# board_design.net
KiCad netlist of a schematic drawn in EAGLE
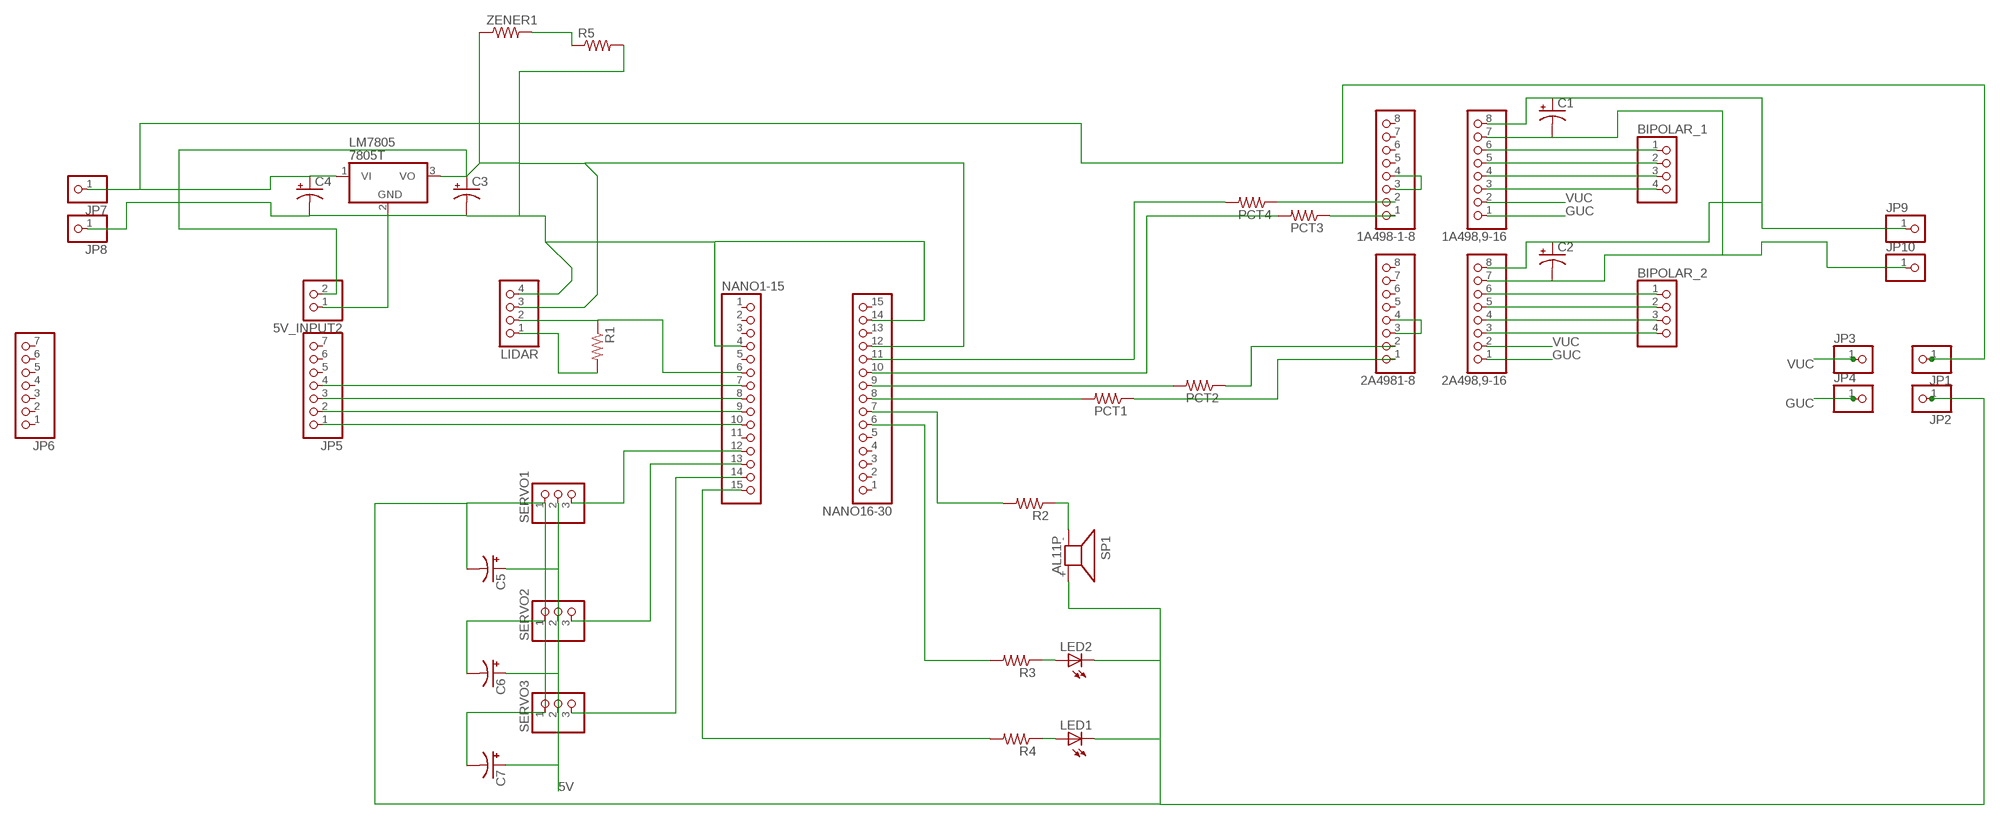
[diagram p0: schematic, sheet 1]

(export (version "E")
  (design (tool "Eeschema 10.0.6"))
  (components
    (comp (ref "1A498,9-16")
      (value "PINHD-1X8")
      (footprint "eagle-import:1X08")
      (libsource (lib "eagle-import") (part "PINHD-1X8"))
    )
    (comp (ref "1A498-1-8")
      (value "PINHD-1X8")
      (footprint "eagle-import:1X08")
      (libsource (lib "eagle-import") (part "PINHD-1X8"))
    )
    (comp (ref "2A498,9-16")
      (value "PINHD-1X8")
      (footprint "eagle-import:1X08")
      (libsource (lib "eagle-import") (part "PINHD-1X8"))
    )
    (comp (ref "2A4981-8")
      (value "PINHD-1X8")
      (footprint "eagle-import:1X08")
      (libsource (lib "eagle-import") (part "PINHD-1X8"))
    )
    (comp (ref "5V_INPUT2")
      (value "PINHD-1X2")
      (footprint "eagle-import:1X02")
      (libsource (lib "eagle-import") (part "PINHD-1X2"))
    )
    (comp (ref "BIPOLAR_1")
      (value "PINHD-1X4")
      (footprint "eagle-import:1X04")
      (libsource (lib "eagle-import") (part "PINHD-1X4"))
    )
    (comp (ref "BIPOLAR_2")
      (value "PINHD-1X4")
      (footprint "eagle-import:1X04")
      (libsource (lib "eagle-import") (part "PINHD-1X4"))
    )
    (comp (ref "C1")
      (value "CPOL-USE2.5-7")
      (footprint "eagle-import:E2,5-7")
      (libsource (lib "eagle-import") (part "CPOL-USE2.5-7"))
    )
    (comp (ref "C2")
      (value "CPOL-USE2.5-7")
      (footprint "eagle-import:E2,5-7")
      (libsource (lib "eagle-import") (part "CPOL-USE2.5-7"))
    )
    (comp (ref "C3")
      (value "CPOL-USE2.5-7")
      (footprint "eagle-import:E2,5-7")
      (libsource (lib "eagle-import") (part "CPOL-USE2.5-7"))
    )
    (comp (ref "C4")
      (value "CPOL-USE2.5-7")
      (footprint "eagle-import:E2,5-7")
      (libsource (lib "eagle-import") (part "CPOL-USE2.5-7"))
    )
    (comp (ref "C5")
      (value "CPOL-USE2.5-7")
      (footprint "eagle-import:E2,5-7")
      (libsource (lib "eagle-import") (part "CPOL-USE2.5-7"))
    )
    (comp (ref "C6")
      (value "CPOL-USE2.5-7")
      (footprint "eagle-import:E2,5-7")
      (libsource (lib "eagle-import") (part "CPOL-USE2.5-7"))
    )
    (comp (ref "C7")
      (value "CPOL-USE2.5-7")
      (footprint "eagle-import:E2,5-7")
      (libsource (lib "eagle-import") (part "CPOL-USE2.5-7"))
    )
    (comp (ref "JP1")
      (value "PINHD-1X1")
      (footprint "eagle-import:1X01")
      (libsource (lib "eagle-import") (part "PINHD-1X1"))
    )
    (comp (ref "JP2")
      (value "PINHD-1X1")
      (footprint "eagle-import:1X01")
      (libsource (lib "eagle-import") (part "PINHD-1X1"))
    )
    (comp (ref "JP3")
      (value "PINHD-1X1")
      (footprint "eagle-import:1X01")
      (libsource (lib "eagle-import") (part "PINHD-1X1"))
    )
    (comp (ref "JP4")
      (value "PINHD-1X1")
      (footprint "eagle-import:1X01")
      (libsource (lib "eagle-import") (part "PINHD-1X1"))
    )
    (comp (ref "JP5")
      (value "PINHD-1X7")
      (footprint "eagle-import:1X07")
      (libsource (lib "eagle-import") (part "PINHD-1X7"))
    )
    (comp (ref "JP6")
      (value "PINHD-1X7")
      (footprint "eagle-import:1X07")
      (libsource (lib "eagle-import") (part "PINHD-1X7"))
    )
    (comp (ref "JP7")
      (value "PINHD-1X1")
      (footprint "eagle-import:1X01")
      (libsource (lib "eagle-import") (part "PINHD-1X1"))
    )
    (comp (ref "JP8")
      (value "PINHD-1X1")
      (footprint "eagle-import:1X01")
      (libsource (lib "eagle-import") (part "PINHD-1X1"))
    )
    (comp (ref "JP9")
      (value "PINHD-1X1")
      (footprint "eagle-import:1X01")
      (libsource (lib "eagle-import") (part "PINHD-1X1"))
    )
    (comp (ref "JP10")
      (value "PINHD-1X1")
      (footprint "eagle-import:1X01")
      (libsource (lib "eagle-import") (part "PINHD-1X1"))
    )
    (comp (ref "LED1")
      (value "LED5MM")
      (footprint "eagle-import:LED5MM")
      (libsource (lib "eagle-import") (part "LED5MM"))
    )
    (comp (ref "LED2")
      (value "LED5MM")
      (footprint "eagle-import:LED5MM")
      (libsource (lib "eagle-import") (part "LED5MM"))
    )
    (comp (ref "LIDAR")
      (value "PINHD-1X4")
      (footprint "eagle-import:1X04")
      (libsource (lib "eagle-import") (part "PINHD-1X4"))
    )
    (comp (ref "LM7805")
      (value "7805T")
      (footprint "eagle-import:TO220H")
      (libsource (lib "eagle-import") (part "78T05"))
    )
    (comp (ref "NANO1-15")
      (value "PINHD-1X15")
      (footprint "eagle-import:1X15")
      (libsource (lib "eagle-import") (part "PINHD-1X15"))
    )
    (comp (ref "NANO16-30")
      (value "PINHD-1X15")
      (footprint "eagle-import:1X15")
      (libsource (lib "eagle-import") (part "PINHD-1X15"))
    )
    (comp (ref "PCT1")
      (value "R-US_0207/10")
      (footprint "eagle-import:0207_10")
      (libsource (lib "eagle-import") (part "R-US_0207/10"))
    )
    (comp (ref "PCT2")
      (value "R-US_0207/10")
      (footprint "eagle-import:0207_10")
      (libsource (lib "eagle-import") (part "R-US_0207/10"))
    )
    (comp (ref "PCT3")
      (value "R-US_0207/10")
      (footprint "eagle-import:0207_10")
      (libsource (lib "eagle-import") (part "R-US_0207/10"))
    )
    (comp (ref "PCT4")
      (value "R-US_0207/10")
      (footprint "eagle-import:0207_10")
      (libsource (lib "eagle-import") (part "R-US_0207/10"))
    )
    (comp (ref "R1")
      (value "R-US_0207/10")
      (footprint "eagle-import:0207_10")
      (libsource (lib "eagle-import") (part "R-US_0207/10"))
    )
    (comp (ref "R2")
      (value "R-US_0207/10")
      (footprint "eagle-import:0207_10")
      (libsource (lib "eagle-import") (part "R-US_0207/10"))
    )
    (comp (ref "R3")
      (value "R-US_0207/10")
      (footprint "eagle-import:0207_10")
      (libsource (lib "eagle-import") (part "R-US_0207/10"))
    )
    (comp (ref "R4")
      (value "R-US_0207/10")
      (footprint "eagle-import:0207_10")
      (libsource (lib "eagle-import") (part "R-US_0207/10"))
    )
    (comp (ref "R5")
      (value "R-US_0207/10")
      (footprint "eagle-import:0207_10")
      (libsource (lib "eagle-import") (part "R-US_0207/10"))
    )
    (comp (ref "SERVO1")
      (value "PINHD-1X3")
      (footprint "eagle-import:1X03")
      (libsource (lib "eagle-import") (part "PINHD-1X3"))
    )
    (comp (ref "SERVO2")
      (value "PINHD-1X3")
      (footprint "eagle-import:1X03")
      (libsource (lib "eagle-import") (part "PINHD-1X3"))
    )
    (comp (ref "SERVO3")
      (value "PINHD-1X3")
      (footprint "eagle-import:1X03")
      (libsource (lib "eagle-import") (part "PINHD-1X3"))
    )
    (comp (ref "SP1")
      (value "AL11P")
      (footprint "eagle-import:AL11P")
      (libsource (lib "eagle-import") (part "AL11P"))
    )
    (comp (ref "ZENER1")
      (value "R-US_0207/10")
      (footprint "eagle-import:0207_10")
      (libsource (lib "eagle-import") (part "R-US_0207/10"))
    )
  )
  (nets
    (net (code "1") (name "/5V") (class "Default")
      (node (ref "C4") (pin "+") (pinfunction "+_+") (pintype "passive"))
      (node (ref "C5") (pin "+") (pinfunction "+_+") (pintype "passive"))
      (node (ref "C6") (pin "+") (pinfunction "+_+") (pintype "passive"))
      (node (ref "C7") (pin "+") (pinfunction "+_+") (pintype "passive"))
      (node (ref "JP1") (pin "1") (pinfunction "1_1") (pintype "passive"))
      (node (ref "JP7") (pin "1") (pinfunction "1_1") (pintype "passive"))
      (node (ref "LM7805") (pin "1") (pinfunction "VI_1") (pintype "input"))
      (node (ref "SERVO1") (pin "2") (pinfunction "2_2") (pintype "passive"))
      (node (ref "SERVO2") (pin "2") (pinfunction "2_2") (pintype "passive"))
      (node (ref "SERVO3") (pin "2") (pinfunction "2_2") (pintype "passive"))
    )
    (net (code "2") (name "/GUC") (class "Default")
      (node (ref "1A498,9-16") (pin "1") (pinfunction "1_1") (pintype "passive"))
      (node (ref "2A498,9-16") (pin "1") (pinfunction "1_1") (pintype "passive"))
      (node (ref "JP4") (pin "1") (pinfunction "1_1") (pintype "passive"))
    )
    (net (code "3") (name "/VUC") (class "Default")
      (node (ref "1A498,9-16") (pin "2") (pinfunction "2_2") (pintype "passive"))
      (node (ref "2A498,9-16") (pin "2") (pinfunction "2_2") (pintype "passive"))
      (node (ref "JP3") (pin "1") (pinfunction "1_1") (pintype "passive"))
    )
    (net (code "4") (name "Net-(1A498,9-16-Pad3)") (class "Default")
      (node (ref "1A498,9-16") (pin "3") (pinfunction "3_3") (pintype "passive"))
      (node (ref "BIPOLAR_1") (pin "4") (pinfunction "4_4") (pintype "passive"))
    )
    (net (code "5") (name "Net-(1A498,9-16-Pad4)") (class "Default")
      (node (ref "1A498,9-16") (pin "4") (pinfunction "4_4") (pintype "passive"))
      (node (ref "BIPOLAR_1") (pin "3") (pinfunction "3_3") (pintype "passive"))
    )
    (net (code "6") (name "Net-(1A498,9-16-Pad5)") (class "Default")
      (node (ref "1A498,9-16") (pin "5") (pinfunction "5_5") (pintype "passive"))
      (node (ref "BIPOLAR_1") (pin "2") (pinfunction "2_2") (pintype "passive"))
    )
    (net (code "7") (name "Net-(1A498,9-16-Pad6)") (class "Default")
      (node (ref "1A498,9-16") (pin "6") (pinfunction "6_6") (pintype "passive"))
      (node (ref "BIPOLAR_1") (pin "1") (pinfunction "1_1") (pintype "passive"))
    )
    (net (code "8") (name "Net-(1A498,9-16-Pad7)") (class "Default")
      (node (ref "1A498,9-16") (pin "7") (pinfunction "7_7") (pintype "passive"))
      (node (ref "2A498,9-16") (pin "7") (pinfunction "7_7") (pintype "passive"))
      (node (ref "C1") (pin "-") (pinfunction "-_-") (pintype "passive"))
      (node (ref "C2") (pin "-") (pinfunction "-_-") (pintype "passive"))
      (node (ref "JP10") (pin "1") (pinfunction "1_1") (pintype "passive"))
    )
    (net (code "9") (name "Net-(1A498,9-16-Pad8)") (class "Default")
      (node (ref "1A498,9-16") (pin "8") (pinfunction "8_8") (pintype "passive"))
      (node (ref "2A498,9-16") (pin "8") (pinfunction "8_8") (pintype "passive"))
      (node (ref "C1") (pin "+") (pinfunction "+_+") (pintype "passive"))
      (node (ref "C2") (pin "+") (pinfunction "+_+") (pintype "passive"))
      (node (ref "JP9") (pin "1") (pinfunction "1_1") (pintype "passive"))
    )
    (net (code "10") (name "Net-(1A498-1-8-Pad1)") (class "Default")
      (node (ref "1A498-1-8") (pin "1") (pinfunction "1_1") (pintype "passive"))
      (node (ref "PCT3") (pin "1") (pinfunction "1_1") (pintype "passive"))
    )
    (net (code "11") (name "Net-(1A498-1-8-Pad2)") (class "Default")
      (node (ref "1A498-1-8") (pin "2") (pinfunction "2_2") (pintype "passive"))
      (node (ref "PCT4") (pin "1") (pinfunction "1_1") (pintype "passive"))
    )
    (net (code "12") (name "Net-(1A498-1-8-Pad3)") (class "Default")
      (node (ref "1A498-1-8") (pin "3") (pinfunction "3_3") (pintype "passive"))
      (node (ref "1A498-1-8") (pin "4") (pinfunction "4_4") (pintype "passive"))
    )
    (net (code "13") (name "Net-(2A498,9-16-Pad3)") (class "Default")
      (node (ref "2A498,9-16") (pin "3") (pinfunction "3_3") (pintype "passive"))
      (node (ref "BIPOLAR_2") (pin "4") (pinfunction "4_4") (pintype "passive"))
    )
    (net (code "14") (name "Net-(2A498,9-16-Pad4)") (class "Default")
      (node (ref "2A498,9-16") (pin "4") (pinfunction "4_4") (pintype "passive"))
      (node (ref "BIPOLAR_2") (pin "3") (pinfunction "3_3") (pintype "passive"))
    )
    (net (code "15") (name "Net-(2A498,9-16-Pad5)") (class "Default")
      (node (ref "2A498,9-16") (pin "5") (pinfunction "5_5") (pintype "passive"))
      (node (ref "BIPOLAR_2") (pin "2") (pinfunction "2_2") (pintype "passive"))
    )
    (net (code "16") (name "Net-(2A498,9-16-Pad6)") (class "Default")
      (node (ref "2A498,9-16") (pin "6") (pinfunction "6_6") (pintype "passive"))
      (node (ref "BIPOLAR_2") (pin "1") (pinfunction "1_1") (pintype "passive"))
    )
    (net (code "17") (name "Net-(2A4981-8-Pad1)") (class "Default")
      (node (ref "2A4981-8") (pin "1") (pinfunction "1_1") (pintype "passive"))
      (node (ref "PCT1") (pin "1") (pinfunction "1_1") (pintype "passive"))
    )
    (net (code "18") (name "Net-(2A4981-8-Pad2)") (class "Default")
      (node (ref "2A4981-8") (pin "2") (pinfunction "2_2") (pintype "passive"))
      (node (ref "PCT2") (pin "1") (pinfunction "1_1") (pintype "passive"))
    )
    (net (code "19") (name "Net-(2A4981-8-Pad3)") (class "Default")
      (node (ref "2A4981-8") (pin "3") (pinfunction "3_3") (pintype "passive"))
      (node (ref "2A4981-8") (pin "4") (pinfunction "4_4") (pintype "passive"))
    )
    (net (code "20") (name "Net-(JP5-Pad1)") (class "Default")
      (node (ref "JP5") (pin "1") (pinfunction "1_1") (pintype "passive"))
      (node (ref "NANO1-15") (pin "10") (pinfunction "10_10") (pintype "passive"))
    )
    (net (code "21") (name "Net-(JP5-Pad2)") (class "Default")
      (node (ref "JP5") (pin "2") (pinfunction "2_2") (pintype "passive"))
      (node (ref "NANO1-15") (pin "9") (pinfunction "9_9") (pintype "passive"))
    )
    (net (code "22") (name "Net-(JP5-Pad3)") (class "Default")
      (node (ref "JP5") (pin "3") (pinfunction "3_3") (pintype "passive"))
      (node (ref "NANO1-15") (pin "8") (pinfunction "8_8") (pintype "passive"))
    )
    (net (code "23") (name "Net-(JP5-Pad4)") (class "Default")
      (node (ref "JP5") (pin "4") (pinfunction "4_4") (pintype "passive"))
      (node (ref "NANO1-15") (pin "7") (pinfunction "7_7") (pintype "passive"))
    )
    (net (code "24") (name "Net-(LED1-C)") (class "Default")
      (node (ref "C5") (pin "-") (pinfunction "-_-") (pintype "passive"))
      (node (ref "C6") (pin "-") (pinfunction "-_-") (pintype "passive"))
      (node (ref "C7") (pin "-") (pinfunction "-_-") (pintype "passive"))
      (node (ref "JP2") (pin "1") (pinfunction "1_1") (pintype "passive"))
      (node (ref "LED1") (pin "K") (pinfunction "C_K") (pintype "passive"))
      (node (ref "LED2") (pin "K") (pinfunction "C_K") (pintype "passive"))
      (node (ref "SERVO1") (pin "1") (pinfunction "1_1") (pintype "passive"))
      (node (ref "SERVO2") (pin "1") (pinfunction "1_1") (pintype "passive"))
      (node (ref "SERVO3") (pin "1") (pinfunction "1_1") (pintype "passive"))
      (node (ref "SP1") (pin "+") (pinfunction "2_+") (pintype "passive"))
    )
    (net (code "25") (name "Net-(LED1-PadA)") (class "Default")
      (node (ref "LED1") (pin "A") (pinfunction "A_A") (pintype "passive"))
      (node (ref "R4") (pin "1") (pinfunction "1_1") (pintype "passive"))
    )
    (net (code "26") (name "Net-(LED2-PadA)") (class "Default")
      (node (ref "LED2") (pin "A") (pinfunction "A_A") (pintype "passive"))
      (node (ref "R3") (pin "1") (pinfunction "1_1") (pintype "passive"))
    )
    (net (code "27") (name "Net-(LIDAR-Pad1)") (class "Default")
      (node (ref "LIDAR") (pin "1") (pinfunction "1_1") (pintype "passive"))
      (node (ref "R1") (pin "2") (pinfunction "2_2") (pintype "passive"))
    )
    (net (code "28") (name "Net-(LIDAR-Pad2)") (class "Default")
      (node (ref "LIDAR") (pin "2") (pinfunction "2_2") (pintype "passive"))
      (node (ref "NANO1-15") (pin "6") (pinfunction "6_6") (pintype "passive"))
      (node (ref "R1") (pin "1") (pinfunction "1_1") (pintype "passive"))
    )
    (net (code "29") (name "Net-(LM7805-GND)") (class "Default")
      (node (ref "5V_INPUT2") (pin "1") (pinfunction "1_1") (pintype "passive"))
      (node (ref "C3") (pin "-") (pinfunction "-_-") (pintype "passive"))
      (node (ref "C4") (pin "-") (pinfunction "-_-") (pintype "passive"))
      (node (ref "JP8") (pin "1") (pinfunction "1_1") (pintype "passive"))
      (node (ref "LIDAR") (pin "4") (pinfunction "4_4") (pintype "passive"))
      (node (ref "LM7805") (pin "2") (pinfunction "GND_2") (pintype "passive"))
      (node (ref "NANO1-15") (pin "4") (pinfunction "4_4") (pintype "passive"))
      (node (ref "NANO16-30") (pin "14") (pinfunction "14_14") (pintype "passive"))
      (node (ref "R5") (pin "2") (pinfunction "2_2") (pintype "passive"))
    )
    (net (code "30") (name "Net-(LM7805-VO)") (class "Default")
      (node (ref "5V_INPUT2") (pin "2") (pinfunction "2_2") (pintype "passive"))
      (node (ref "C3") (pin "+") (pinfunction "+_+") (pintype "passive"))
      (node (ref "LIDAR") (pin "3") (pinfunction "3_3") (pintype "passive"))
      (node (ref "LM7805") (pin "3") (pinfunction "VO_3") (pintype "passive"))
      (node (ref "NANO16-30") (pin "12") (pinfunction "12_12") (pintype "passive"))
      (node (ref "ZENER1") (pin "1") (pinfunction "1_1") (pintype "passive"))
    )
    (net (code "31") (name "Net-(NANO1-15-Pad12)") (class "Default")
      (node (ref "NANO1-15") (pin "12") (pinfunction "12_12") (pintype "passive"))
      (node (ref "SERVO1") (pin "3") (pinfunction "3_3") (pintype "passive"))
    )
    (net (code "32") (name "Net-(NANO1-15-Pad13)") (class "Default")
      (node (ref "NANO1-15") (pin "13") (pinfunction "13_13") (pintype "passive"))
      (node (ref "SERVO2") (pin "3") (pinfunction "3_3") (pintype "passive"))
    )
    (net (code "33") (name "Net-(NANO1-15-Pad14)") (class "Default")
      (node (ref "NANO1-15") (pin "14") (pinfunction "14_14") (pintype "passive"))
      (node (ref "SERVO3") (pin "3") (pinfunction "3_3") (pintype "passive"))
    )
    (net (code "34") (name "Net-(NANO1-15-Pad15)") (class "Default")
      (node (ref "NANO1-15") (pin "15") (pinfunction "15_15") (pintype "passive"))
      (node (ref "R4") (pin "2") (pinfunction "2_2") (pintype "passive"))
    )
    (net (code "35") (name "Net-(NANO16-30-Pad6)") (class "Default")
      (node (ref "NANO16-30") (pin "6") (pinfunction "6_6") (pintype "passive"))
      (node (ref "R3") (pin "2") (pinfunction "2_2") (pintype "passive"))
    )
    (net (code "36") (name "Net-(NANO16-30-Pad7)") (class "Default")
      (node (ref "NANO16-30") (pin "7") (pinfunction "7_7") (pintype "passive"))
      (node (ref "R2") (pin "2") (pinfunction "2_2") (pintype "passive"))
    )
    (net (code "37") (name "Net-(NANO16-30-Pad8)") (class "Default")
      (node (ref "NANO16-30") (pin "8") (pinfunction "8_8") (pintype "passive"))
      (node (ref "PCT1") (pin "2") (pinfunction "2_2") (pintype "passive"))
    )
    (net (code "38") (name "Net-(NANO16-30-Pad9)") (class "Default")
      (node (ref "NANO16-30") (pin "9") (pinfunction "9_9") (pintype "passive"))
      (node (ref "PCT2") (pin "2") (pinfunction "2_2") (pintype "passive"))
    )
    (net (code "39") (name "Net-(NANO16-30-Pad10)") (class "Default")
      (node (ref "NANO16-30") (pin "10") (pinfunction "10_10") (pintype "passive"))
      (node (ref "PCT3") (pin "2") (pinfunction "2_2") (pintype "passive"))
    )
    (net (code "40") (name "Net-(NANO16-30-Pad11)") (class "Default")
      (node (ref "NANO16-30") (pin "11") (pinfunction "11_11") (pintype "passive"))
      (node (ref "PCT4") (pin "2") (pinfunction "2_2") (pintype "passive"))
    )
    (net (code "41") (name "Net-(R5-Pad1)") (class "Default")
      (node (ref "R5") (pin "1") (pinfunction "1_1") (pintype "passive"))
      (node (ref "ZENER1") (pin "2") (pinfunction "2_2") (pintype "passive"))
    )
    (net (code "42") (name "Net-(SP1-1)") (class "Default")
      (node (ref "R2") (pin "1") (pinfunction "1_1") (pintype "passive"))
      (node (ref "SP1") (pin "-") (pinfunction "1_-") (pintype "passive"))
    )
    (net (code "43") (name "unconnected-(1A498-1-8-Pad5)") (class "Default")
      (node (ref "1A498-1-8") (pin "5") (pinfunction "5_5") (pintype "passive"))
    )
    (net (code "44") (name "unconnected-(1A498-1-8-Pad6)") (class "Default")
      (node (ref "1A498-1-8") (pin "6") (pinfunction "6_6") (pintype "passive"))
    )
    (net (code "45") (name "unconnected-(1A498-1-8-Pad7)") (class "Default")
      (node (ref "1A498-1-8") (pin "7") (pinfunction "7_7") (pintype "passive"))
    )
    (net (code "46") (name "unconnected-(1A498-1-8-Pad8)") (class "Default")
      (node (ref "1A498-1-8") (pin "8") (pinfunction "8_8") (pintype "passive"))
    )
    (net (code "47") (name "unconnected-(2A4981-8-Pad5)") (class "Default")
      (node (ref "2A4981-8") (pin "5") (pinfunction "5_5") (pintype "passive"))
    )
    (net (code "48") (name "unconnected-(2A4981-8-Pad6)") (class "Default")
      (node (ref "2A4981-8") (pin "6") (pinfunction "6_6") (pintype "passive"))
    )
    (net (code "49") (name "unconnected-(2A4981-8-Pad7)") (class "Default")
      (node (ref "2A4981-8") (pin "7") (pinfunction "7_7") (pintype "passive"))
    )
    (net (code "50") (name "unconnected-(2A4981-8-Pad8)") (class "Default")
      (node (ref "2A4981-8") (pin "8") (pinfunction "8_8") (pintype "passive"))
    )
    (net (code "51") (name "unconnected-(JP5-Pad5)") (class "Default")
      (node (ref "JP5") (pin "5") (pinfunction "5_5") (pintype "passive"))
    )
    (net (code "52") (name "unconnected-(JP5-Pad6)") (class "Default")
      (node (ref "JP5") (pin "6") (pinfunction "6_6") (pintype "passive"))
    )
    (net (code "53") (name "unconnected-(JP5-Pad7)") (class "Default")
      (node (ref "JP5") (pin "7") (pinfunction "7_7") (pintype "passive"))
    )
    (net (code "54") (name "unconnected-(JP6-Pad1)") (class "Default")
      (node (ref "JP6") (pin "1") (pinfunction "1_1") (pintype "passive"))
    )
    (net (code "55") (name "unconnected-(JP6-Pad2)") (class "Default")
      (node (ref "JP6") (pin "2") (pinfunction "2_2") (pintype "passive"))
    )
    (net (code "56") (name "unconnected-(JP6-Pad3)") (class "Default")
      (node (ref "JP6") (pin "3") (pinfunction "3_3") (pintype "passive"))
    )
    (net (code "57") (name "unconnected-(JP6-Pad4)") (class "Default")
      (node (ref "JP6") (pin "4") (pinfunction "4_4") (pintype "passive"))
    )
    (net (code "58") (name "unconnected-(JP6-Pad5)") (class "Default")
      (node (ref "JP6") (pin "5") (pinfunction "5_5") (pintype "passive"))
    )
    (net (code "59") (name "unconnected-(JP6-Pad6)") (class "Default")
      (node (ref "JP6") (pin "6") (pinfunction "6_6") (pintype "passive"))
    )
    (net (code "60") (name "unconnected-(JP6-Pad7)") (class "Default")
      (node (ref "JP6") (pin "7") (pinfunction "7_7") (pintype "passive"))
    )
    (net (code "61") (name "unconnected-(NANO1-15-Pad1)") (class "Default")
      (node (ref "NANO1-15") (pin "1") (pinfunction "1_1") (pintype "passive"))
    )
    (net (code "62") (name "unconnected-(NANO1-15-Pad2)") (class "Default")
      (node (ref "NANO1-15") (pin "2") (pinfunction "2_2") (pintype "passive"))
    )
    (net (code "63") (name "unconnected-(NANO1-15-Pad3)") (class "Default")
      (node (ref "NANO1-15") (pin "3") (pinfunction "3_3") (pintype "passive"))
    )
    (net (code "64") (name "unconnected-(NANO1-15-Pad5)") (class "Default")
      (node (ref "NANO1-15") (pin "5") (pinfunction "5_5") (pintype "passive"))
    )
    (net (code "65") (name "unconnected-(NANO1-15-Pad11)") (class "Default")
      (node (ref "NANO1-15") (pin "11") (pinfunction "11_11") (pintype "passive"))
    )
    (net (code "66") (name "unconnected-(NANO16-30-Pad1)") (class "Default")
      (node (ref "NANO16-30") (pin "1") (pinfunction "1_1") (pintype "passive"))
    )
    (net (code "67") (name "unconnected-(NANO16-30-Pad2)") (class "Default")
      (node (ref "NANO16-30") (pin "2") (pinfunction "2_2") (pintype "passive"))
    )
    (net (code "68") (name "unconnected-(NANO16-30-Pad3)") (class "Default")
      (node (ref "NANO16-30") (pin "3") (pinfunction "3_3") (pintype "passive"))
    )
    (net (code "69") (name "unconnected-(NANO16-30-Pad4)") (class "Default")
      (node (ref "NANO16-30") (pin "4") (pinfunction "4_4") (pintype "passive"))
    )
    (net (code "70") (name "unconnected-(NANO16-30-Pad5)") (class "Default")
      (node (ref "NANO16-30") (pin "5") (pinfunction "5_5") (pintype "passive"))
    )
    (net (code "71") (name "unconnected-(NANO16-30-Pad13)") (class "Default")
      (node (ref "NANO16-30") (pin "13") (pinfunction "13_13") (pintype "passive"))
    )
    (net (code "72") (name "unconnected-(NANO16-30-Pad15)") (class "Default")
      (node (ref "NANO16-30") (pin "15") (pinfunction "15_15") (pintype "passive"))
    )
  )
)
